# Power5V.net
KiCad netlist of a schematic drawn in Altium Designer
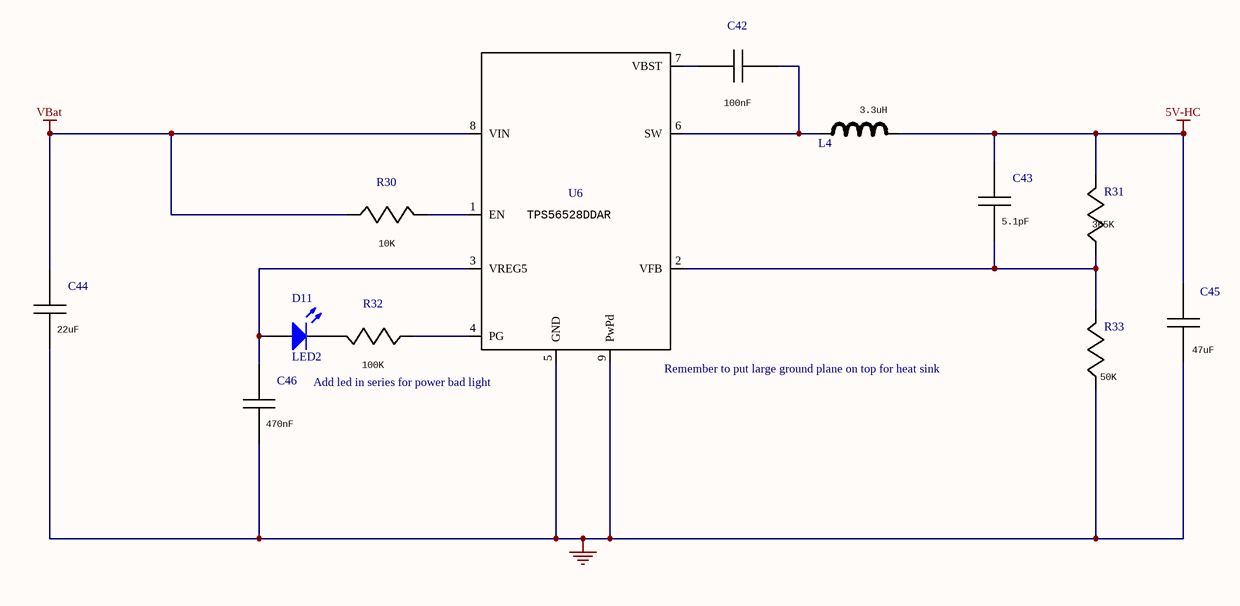
[diagram p0: Power5V.SchDoc]

(export (version "E")
  (design (tool "Eeschema 10.0.6"))
  (components
    (comp (ref "C42")
      (value "100nF")
      (footprint "1608")
      (description "Imported")
      (fields (field (name "MANUFACTURER_PART_NUMBER") "C1005X5R1A104K"))
      (libsource (lib "TI WEBENCH") (part "C1005X5R1A104K"))
    )
    (comp (ref "C43")
      (value "5.1pF")
      (footprint "1608")
      (description "Imported")
      (fields
        (field (name "MANUFACTURER_PART_NUMBER") "GRM1555C1E5R1CA01D")
        (field (name "Comment") "GRM1555C1E5R1CA0")
      )
      (libsource (lib "TI WEBENCH") (part "GRM1555C1E5R1CA0"))
    )
    (comp (ref "C44")
      (value "22uF")
      (footprint "1210")
      (description "Imported")
      (fields
        (field (name "MANUFACTURER_PART_NUMBER") "GRM32ER61E226KE15L")
        (field (name "Comment") "GRM32ER61E226KE1")
      )
      (libsource (lib "TI WEBENCH") (part "GRM32ER61E226KE1"))
    )
    (comp (ref "C45")
      (value "47uF")
      (footprint "1210")
      (description "Imported")
      (fields (field (name "MANUFACTURER_PART_NUMBER") "C3216X6S1A476M"))
      (libsource (lib "TI WEBENCH") (part "C3216X6S1A476M"))
    )
    (comp (ref "C46")
      (value "470nF")
      (footprint "1608")
      (description "Imported")
      (fields
        (field (name "MANUFACTURER_PART_NUMBER") "GRM155R61A474KE15D")
        (field (name "Comment") "GRM155R61A474KE1")
      )
      (libsource (lib "TI WEBENCH") (part "GRM155R61A474KE1"))
    )
    (comp (ref "D11")
      (value "LED2")
      (footprint "1608[0603]")
      (description "Typical RED, GREEN, YELLOW, AMBER GaAs LED")
      (fields (field (name "PUBLISHER") "Altium Limited"))
      (libsource (lib "Miscellaneous Devices") (part "LED2"))
    )
    (comp (ref "L4")
      (value "3.3uH")
      (footprint "IHLP-3232DZ")
      (description "Imported")
      (fields
        (field (name "MANUFACTURER_PART_NUMBER") "IHLP3232DZER3R3M01")
        (field (name "MANUFACTURER") "Vishay")
      )
      (libsource (lib "TI WEBENCH") (part "IHLP3232DZER3R3M"))
    )
    (comp (ref "R30")
      (value "10K")
      (footprint "1608")
      (description "Imported")
      (fields (field (name "MANUFACTURER_PART_NUMBER") "CRCW040210K0FKED"))
      (libsource (lib "TI WEBENCH") (part "CRCW040210K0FKED"))
    )
    (comp (ref "R31")
      (value "365K")
      (footprint "1608")
      (description "Imported")
      (fields (field (name "MANUFACTURER_PART_NUMBER") "CRCW0402365KFKED"))
      (libsource (lib "TI WEBENCH") (part "CRCW0402365KFKED"))
    )
    (comp (ref "R32")
      (value "100K")
      (footprint "1608")
      (description "Imported")
      (fields (field (name "MANUFACTURER_PART_NUMBER") "CRCW0402100KFKED"))
      (libsource (lib "TI WEBENCH") (part "CRCW0402100KFKED"))
    )
    (comp (ref "R33")
      (value "50K")
      (footprint "1608")
      (description "Imported")
      (fields (field (name "MANUFACTURER_PART_NUMBER") "CRCW040249K9FKED"))
      (libsource (lib "TI WEBENCH") (part "CRCW040249K9FKED"))
    )
    (comp (ref "U6")
      (value "TPS56528DDAR")
      (footprint "R-PDSO-G8")
      (description "Imported")
      (fields (field (name "MANUFACTURER_PART_NUMBER") "TPS56528DDAR"))
      (libsource (lib "TI WEBENCH") (part "TPS56528DDAR"))
    )
  )
  (nets
    (net (code "1") (name "5V-HC") (class "Default")
      (node (ref "C43") (pin "1") (pinfunction "1_1") (pintype "passive"))
      (node (ref "C45") (pin "1") (pinfunction "1_1") (pintype "passive"))
      (node (ref "L4") (pin "2") (pinfunction "2_2") (pintype "passive"))
      (node (ref "R31") (pin "1") (pinfunction "1_1") (pintype "passive"))
    )
    (net (code "2") (name "GND") (class "Default")
      (node (ref "C44") (pin "2") (pinfunction "2_2") (pintype "passive"))
      (node (ref "C45") (pin "2") (pinfunction "2_2") (pintype "passive"))
      (node (ref "C46") (pin "2") (pinfunction "2_2") (pintype "passive"))
      (node (ref "R33") (pin "2") (pinfunction "2_2") (pintype "passive"))
      (node (ref "U6") (pin "5") (pinfunction "GND_5") (pintype "passive"))
      (node (ref "U6") (pin "9") (pinfunction "PwPd_9") (pintype "passive"))
    )
    (net (code "3") (name "Net-(D11-A)") (class "Default")
      (node (ref "C46") (pin "1") (pinfunction "1_1") (pintype "passive"))
      (node (ref "D11") (pin "1") (pinfunction "A_1") (pintype "passive"))
      (node (ref "U6") (pin "3") (pinfunction "VREG5_3") (pintype "passive"))
    )
    (net (code "4") (name "Net-(D11-K)") (class "Default")
      (node (ref "D11") (pin "2") (pinfunction "K_2") (pintype "passive"))
      (node (ref "R32") (pin "1") (pinfunction "1_1") (pintype "passive"))
    )
    (net (code "5") (name "Net-(U6-EN)") (class "Default")
      (node (ref "R30") (pin "1") (pinfunction "1_1") (pintype "passive"))
      (node (ref "U6") (pin "1") (pinfunction "EN_1") (pintype "passive"))
    )
    (net (code "6") (name "Net-(U6-PG)") (class "Default")
      (node (ref "R32") (pin "2") (pinfunction "2_2") (pintype "passive"))
      (node (ref "U6") (pin "4") (pinfunction "PG_4") (pintype "passive"))
    )
    (net (code "7") (name "Net-(U6-SW)") (class "Default")
      (node (ref "C42") (pin "2") (pinfunction "2_2") (pintype "passive"))
      (node (ref "L4") (pin "1") (pinfunction "1_1") (pintype "passive"))
      (node (ref "U6") (pin "6") (pinfunction "SW_6") (pintype "passive"))
    )
    (net (code "8") (name "Net-(U6-VBST)") (class "Default")
      (node (ref "C42") (pin "1") (pinfunction "1_1") (pintype "passive"))
      (node (ref "U6") (pin "7") (pinfunction "VBST_7") (pintype "passive"))
    )
    (net (code "9") (name "Net-(U6-VFB)") (class "Default")
      (node (ref "C43") (pin "2") (pinfunction "2_2") (pintype "passive"))
      (node (ref "R31") (pin "2") (pinfunction "2_2") (pintype "passive"))
      (node (ref "R33") (pin "1") (pinfunction "1_1") (pintype "passive"))
      (node (ref "U6") (pin "2") (pinfunction "VFB_2") (pintype "passive"))
    )
    (net (code "10") (name "VBat") (class "Default")
      (node (ref "C44") (pin "1") (pinfunction "1_1") (pintype "passive"))
      (node (ref "R30") (pin "2") (pinfunction "2_2") (pintype "passive"))
      (node (ref "U6") (pin "8") (pinfunction "VIN_8") (pintype "passive"))
    )
  )
)
